# DSP.net
KiCad netlist of a schematic drawn in Altium Designer
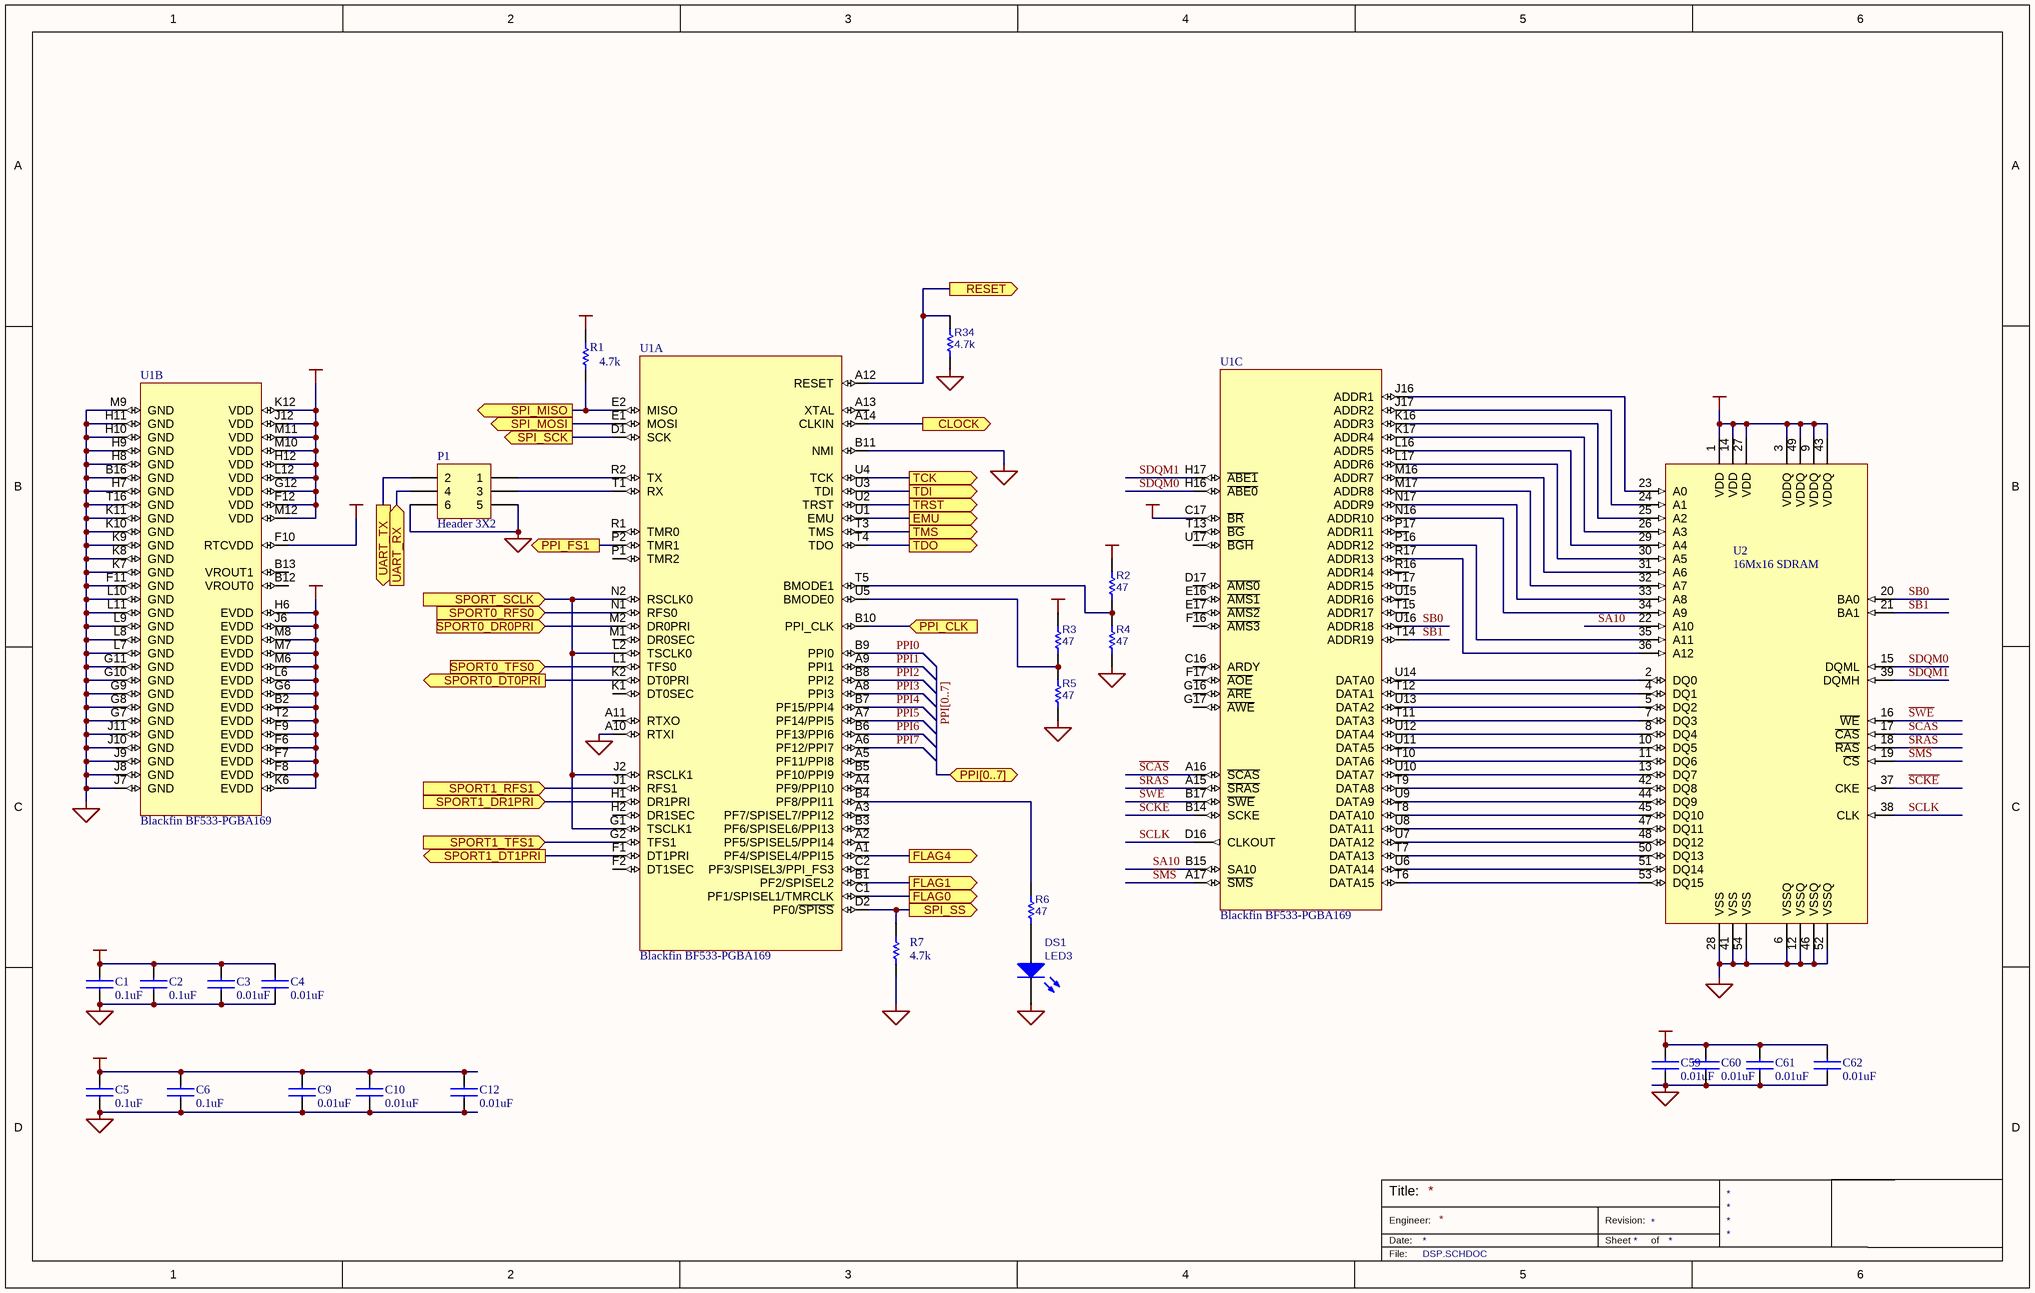
[diagram p0: DSP.SCHDOC]

(export (version "E")
  (design (tool "Eeschema 10.0.6"))
  (components
    (comp (ref "C1")
      (value "0.1uF")
      (footprint "0603")
      (description "Standard Capacitor")
      (fields (field (name "Comment") "CAPACITOR"))
      (libsource (lib "parts") (part "CAPACITOR"))
    )
    (comp (ref "C2")
      (value "0.1uF")
      (footprint "0603")
      (description "Standard Capacitor")
      (fields (field (name "Comment") "CAPACITOR"))
      (libsource (lib "parts") (part "CAPACITOR"))
    )
    (comp (ref "C3")
      (value "0.01uF")
      (footprint "0402")
      (description "Standard Capacitor")
      (fields (field (name "Comment") "CAPACITOR"))
      (libsource (lib "parts") (part "CAPACITOR"))
    )
    (comp (ref "C4")
      (value "0.01uF")
      (footprint "0402")
      (description "Standard Capacitor")
      (fields (field (name "Comment") "CAPACITOR"))
      (libsource (lib "parts") (part "CAPACITOR"))
    )
    (comp (ref "C5")
      (value "0.1uF")
      (footprint "0603")
      (description "Standard Capacitor")
      (fields (field (name "Comment") "CAPACITOR"))
      (libsource (lib "parts") (part "CAPACITOR"))
    )
    (comp (ref "C6")
      (value "0.1uF")
      (footprint "0603")
      (description "Standard Capacitor")
      (fields (field (name "Comment") "CAPACITOR"))
      (libsource (lib "parts") (part "CAPACITOR"))
    )
    (comp (ref "C9")
      (value "0.01uF")
      (footprint "0402")
      (description "Standard Capacitor")
      (fields (field (name "Comment") "CAPACITOR"))
      (libsource (lib "parts") (part "CAPACITOR"))
    )
    (comp (ref "C10")
      (value "0.01uF")
      (footprint "0402")
      (description "Standard Capacitor")
      (fields (field (name "Comment") "CAPACITOR"))
      (libsource (lib "parts") (part "CAPACITOR"))
    )
    (comp (ref "C12")
      (value "0.01uF")
      (footprint "0402")
      (description "Standard Capacitor")
      (fields (field (name "Comment") "CAPACITOR"))
      (libsource (lib "parts") (part "CAPACITOR"))
    )
    (comp (ref "C59")
      (value "0.01uF")
      (footprint "0402")
      (description "Standard Capacitor")
      (fields (field (name "Comment") "CAPACITOR"))
      (libsource (lib "parts") (part "CAPACITOR"))
    )
    (comp (ref "C60")
      (value "0.01uF")
      (footprint "0402")
      (description "Standard Capacitor")
      (fields (field (name "Comment") "CAPACITOR"))
      (libsource (lib "parts") (part "CAPACITOR"))
    )
    (comp (ref "C61")
      (value "0.01uF")
      (footprint "0402")
      (description "Standard Capacitor")
      (fields (field (name "Comment") "CAPACITOR"))
      (libsource (lib "parts") (part "CAPACITOR"))
    )
    (comp (ref "C62")
      (value "0.01uF")
      (footprint "0402")
      (description "Standard Capacitor")
      (fields (field (name "Comment") "CAPACITOR"))
      (libsource (lib "parts") (part "CAPACITOR"))
    )
    (comp (ref "DS1")
      (value "LED3")
      (footprint "LED0805")
      (description "Typical BLUE SiC LED")
      (fields (field (name "PUBLISHER") "Altium Limited"))
      (libsource (lib "Miscellaneous Devices") (part "LED3"))
    )
    (comp (ref "P1")
      (value "Header 3X2")
      (footprint "HDR2X3")
      (description "Header, 3-Pin, Dual row")
      (fields (field (name "PUBLISHER") "Altium Limited"))
      (libsource (lib "Miscellaneous Connectors") (part "Header 3X2"))
    )
    (comp (ref "R1")
      (value "4.7k")
      (footprint "0603")
      (description "Standard Passive Resistor")
      (fields (field (name "TOLERANCE") "1%") (field (name "Comment") "RESISTOR"))
      (libsource (lib "parts") (part "RESISTOR"))
    )
    (comp (ref "R2")
      (value "47")
      (footprint "0603")
      (description "Standard Passive Resistor")
      (fields (field (name "TOLERANCE") "1%") (field (name "Comment") "RESISTOR"))
      (libsource (lib "parts") (part "RESISTOR"))
    )
    (comp (ref "R3")
      (value "47")
      (footprint "0603")
      (description "Standard Passive Resistor")
      (fields (field (name "TOLERANCE") "1%") (field (name "Comment") "RESISTOR"))
      (libsource (lib "parts") (part "RESISTOR"))
    )
    (comp (ref "R4")
      (value "47")
      (footprint "0603")
      (description "Standard Passive Resistor")
      (fields (field (name "TOLERANCE") "1%") (field (name "Comment") "RESISTOR"))
      (libsource (lib "parts") (part "RESISTOR"))
    )
    (comp (ref "R5")
      (value "47")
      (footprint "0603")
      (description "Standard Passive Resistor")
      (fields (field (name "TOLERANCE") "1%") (field (name "Comment") "RESISTOR"))
      (libsource (lib "parts") (part "RESISTOR"))
    )
    (comp (ref "R6")
      (value "47")
      (footprint "0603")
      (description "Standard Passive Resistor")
      (fields (field (name "TOLERANCE") "1%") (field (name "Comment") "RESISTOR"))
      (libsource (lib "parts") (part "RESISTOR"))
    )
    (comp (ref "R7")
      (value "4.7k")
      (footprint "0603")
      (description "Standard Passive Resistor")
      (fields (field (name "TOLERANCE") "1%") (field (name "Comment") "RESISTOR"))
      (libsource (lib "parts") (part "RESISTOR"))
    )
    (comp (ref "R34")
      (value "4.7k")
      (footprint "0603")
      (description "Standard Passive Resistor")
      (fields (field (name "TOLERANCE") "1%") (field (name "Comment") "RESISTOR"))
      (libsource (lib "parts") (part "RESISTOR"))
    )
    (comp (ref "U1")
      (value "Blackfin BF533-PGBA169")
      (footprint "AD PBGA-169")
      (description "Analog Devices Blackfin")
      (libsource (lib "parts") (part "ADSP-BF53x-PBGA169"))
    )
    (comp (ref "U2")
      (value "16Mx16 SDRAM")
      (footprint "SO-G54/X.5")
      (description "Micron 16Mbitx16 SDRAM")
      (libsource (lib "parts") (part "MT48LC16M16A2TG"))
    )
  )
  (nets
    (net (code "1") (name "+1.2VCC") (class "Default")
      (node (ref "C1") (pin "2") (pintype "passive"))
      (node (ref "C2") (pin "2") (pintype "passive"))
      (node (ref "C3") (pin "2") (pintype "passive"))
      (node (ref "C4") (pin "2") (pintype "passive"))
      (node (ref "U1") (pin "F12") (pinfunction "VDD_F12") (pintype "bidirectional"))
      (node (ref "U1") (pin "G12") (pinfunction "VDD_G12") (pintype "bidirectional"))
      (node (ref "U1") (pin "H12") (pinfunction "VDD_H12") (pintype "bidirectional"))
      (node (ref "U1") (pin "J12") (pinfunction "VDD_J12") (pintype "bidirectional"))
      (node (ref "U1") (pin "K12") (pinfunction "VDD_K12") (pintype "bidirectional"))
      (node (ref "U1") (pin "L12") (pinfunction "VDD_L12") (pintype "bidirectional"))
      (node (ref "U1") (pin "M10") (pinfunction "VDD_M10") (pintype "bidirectional"))
      (node (ref "U1") (pin "M11") (pinfunction "VDD_M11") (pintype "bidirectional"))
      (node (ref "U1") (pin "M12") (pinfunction "VDD_M12") (pintype "bidirectional"))
    )
    (net (code "2") (name "/CLOCK") (class "Default")
      (node (ref "U1") (pin "A14") (pinfunction "CLKIN_A14") (pintype "bidirectional"))
    )
    (net (code "3") (name "/EMU") (class "Default")
      (node (ref "U1") (pin "U1") (pinfunction "EMU_U1") (pintype "bidirectional"))
    )
    (net (code "4") (name "/FLAG0") (class "Default")
      (node (ref "U1") (pin "C1") (pinfunction "PF1/SPISEL1/TMRCLK_C1") (pintype "bidirectional"))
    )
    (net (code "5") (name "/FLAG1") (class "Default")
      (node (ref "U1") (pin "B1") (pinfunction "PF2/SPISEL2_B1") (pintype "bidirectional"))
    )
    (net (code "6") (name "/FLAG4") (class "Default")
      (node (ref "U1") (pin "A1") (pinfunction "PF4/SPISEL4/PPI15_A1") (pintype "bidirectional"))
    )
    (net (code "7") (name "/PPI0") (class "Default")
      (node (ref "U1") (pin "B9") (pinfunction "PPI0_B9") (pintype "bidirectional"))
    )
    (net (code "8") (name "/PPI1") (class "Default")
      (node (ref "U1") (pin "A9") (pinfunction "PPI1_A9") (pintype "bidirectional"))
    )
    (net (code "9") (name "/PPI2") (class "Default")
      (node (ref "U1") (pin "B8") (pinfunction "PPI2_B8") (pintype "bidirectional"))
    )
    (net (code "10") (name "/PPI3") (class "Default")
      (node (ref "U1") (pin "A8") (pinfunction "PPI3_A8") (pintype "bidirectional"))
    )
    (net (code "11") (name "/PPI4") (class "Default")
      (node (ref "U1") (pin "B7") (pinfunction "PF15/PPI4_B7") (pintype "bidirectional"))
    )
    (net (code "12") (name "/PPI5") (class "Default")
      (node (ref "U1") (pin "A7") (pinfunction "PF14/PPI5_A7") (pintype "bidirectional"))
    )
    (net (code "13") (name "/PPI6") (class "Default")
      (node (ref "U1") (pin "B6") (pinfunction "PF13/PPI6_B6") (pintype "bidirectional"))
    )
    (net (code "14") (name "/PPI7") (class "Default")
      (node (ref "U1") (pin "A6") (pinfunction "PF12/PPI7_A6") (pintype "bidirectional"))
    )
    (net (code "16") (name "/PPI_CLK") (class "Default")
      (node (ref "U1") (pin "B10") (pinfunction "PPI_CLK_B10") (pintype "bidirectional"))
    )
    (net (code "17") (name "/PPI_FS1") (class "Default")
      (node (ref "U1") (pin "P2") (pinfunction "TMR1_P2") (pintype "bidirectional"))
    )
    (net (code "18") (name "/RESET") (class "Default")
      (node (ref "R34") (pin "1") (pintype "passive"))
      (node (ref "U1") (pin "A12") (pinfunction "RESET_A12") (pintype "bidirectional"))
    )
    (net (code "19") (name "/SA10") (class "Default")
      (node (ref "U1") (pin "B15") (pinfunction "SA10_B15") (pintype "bidirectional"))
      (node (ref "U2") (pin "22") (pinfunction "A10_22") (pintype "input"))
    )
    (net (code "20") (name "/SB0") (class "Default")
      (node (ref "U1") (pin "U16") (pinfunction "ADDR18_U16") (pintype "bidirectional"))
      (node (ref "U2") (pin "20") (pinfunction "BA0_20") (pintype "input"))
    )
    (net (code "21") (name "/SB1") (class "Default")
      (node (ref "U1") (pin "T14") (pinfunction "ADDR19_T14") (pintype "bidirectional"))
      (node (ref "U2") (pin "21") (pinfunction "BA1_21") (pintype "input"))
    )
    (net (code "22") (name "/SCLK") (class "Default")
      (node (ref "U1") (pin "D16") (pinfunction "CLKOUT_D16") (pintype "output"))
      (node (ref "U2") (pin "38") (pinfunction "CLK_38") (pintype "input"))
    )
    (net (code "23") (name "/SDQM0") (class "Default")
      (node (ref "U1") (pin "H16") (pinfunction "~{ABE0}_H16") (pintype "bidirectional"))
      (node (ref "U2") (pin "15") (pinfunction "DQML_15") (pintype "input"))
    )
    (net (code "24") (name "/SDQM1") (class "Default")
      (node (ref "U1") (pin "H17") (pinfunction "~{ABE1}_H17") (pintype "bidirectional"))
      (node (ref "U2") (pin "39") (pinfunction "DQMH_39") (pintype "input"))
    )
    (net (code "25") (name "/SPI_MISO") (class "Default")
      (node (ref "R1") (pin "1") (pintype "passive"))
      (node (ref "U1") (pin "E2") (pinfunction "MISO_E2") (pintype "bidirectional"))
    )
    (net (code "26") (name "/SPI_MOSI") (class "Default")
      (node (ref "U1") (pin "E1") (pinfunction "MOSI_E1") (pintype "bidirectional"))
    )
    (net (code "27") (name "/SPI_SCK") (class "Default")
      (node (ref "U1") (pin "D1") (pinfunction "SCK_D1") (pintype "bidirectional"))
    )
    (net (code "28") (name "/SPI_SS") (class "Default")
      (node (ref "R7") (pin "2") (pintype "passive"))
      (node (ref "U1") (pin "D2") (pinfunction "PF0/~{SPISS}_D2") (pintype "bidirectional"))
    )
    (net (code "29") (name "/SPORT0_DR0PRI") (class "Default")
      (node (ref "U1") (pin "M2") (pinfunction "DR0PRI_M2") (pintype "bidirectional"))
    )
    (net (code "30") (name "/SPORT0_DT0PRI") (class "Default")
      (node (ref "U1") (pin "K2") (pinfunction "DT0PRI_K2") (pintype "bidirectional"))
    )
    (net (code "31") (name "/SPORT0_RFS0") (class "Default")
      (node (ref "U1") (pin "N1") (pinfunction "RFS0_N1") (pintype "bidirectional"))
    )
    (net (code "32") (name "/SPORT0_TFS0") (class "Default")
      (node (ref "U1") (pin "L1") (pinfunction "TFS0_L1") (pintype "bidirectional"))
    )
    (net (code "33") (name "/SPORT1_DR1PRI") (class "Default")
      (node (ref "U1") (pin "H1") (pinfunction "DR1PRI_H1") (pintype "bidirectional"))
    )
    (net (code "34") (name "/SPORT1_DT1PRI") (class "Default")
      (node (ref "U1") (pin "F1") (pinfunction "DT1PRI_F1") (pintype "bidirectional"))
    )
    (net (code "35") (name "/SPORT1_RFS1") (class "Default")
      (node (ref "U1") (pin "J1") (pinfunction "RFS1_J1") (pintype "bidirectional"))
    )
    (net (code "36") (name "/SPORT1_TFS1") (class "Default")
      (node (ref "U1") (pin "G2") (pinfunction "TFS1_G2") (pintype "bidirectional"))
    )
    (net (code "37") (name "/SPORT_SCLK") (class "Default")
      (node (ref "U1") (pin "G1") (pinfunction "TSCLK1_G1") (pintype "bidirectional"))
      (node (ref "U1") (pin "J2") (pinfunction "RSCLK1_J2") (pintype "bidirectional"))
      (node (ref "U1") (pin "L2") (pinfunction "TSCLK0_L2") (pintype "bidirectional"))
      (node (ref "U1") (pin "N2") (pinfunction "RSCLK0_N2") (pintype "bidirectional"))
    )
    (net (code "38") (name "/TCK") (class "Default")
      (node (ref "U1") (pin "U4") (pinfunction "TCK_U4") (pintype "bidirectional"))
    )
    (net (code "39") (name "/TDI") (class "Default")
      (node (ref "U1") (pin "U3") (pinfunction "TDI_U3") (pintype "bidirectional"))
    )
    (net (code "40") (name "/TDO") (class "Default")
      (node (ref "U1") (pin "T4") (pinfunction "TDO_T4") (pintype "bidirectional"))
    )
    (net (code "41") (name "/TMS") (class "Default")
      (node (ref "U1") (pin "T3") (pinfunction "TMS_T3") (pintype "bidirectional"))
    )
    (net (code "42") (name "/TRST") (class "Default")
      (node (ref "U1") (pin "U2") (pinfunction "TRST_U2") (pintype "bidirectional"))
    )
    (net (code "43") (name "/UART_RX") (class "Default")
      (node (ref "P1") (pin "4") (pinfunction "4_4") (pintype "passive"))
    )
    (net (code "44") (name "/UART_TX") (class "Default")
      (node (ref "P1") (pin "2") (pinfunction "2_2") (pintype "passive"))
    )
    (net (code "45") (name "/~{SCAS}") (class "Default")
      (node (ref "U1") (pin "A16") (pinfunction "~{SCAS}_A16") (pintype "bidirectional"))
      (node (ref "U2") (pin "17") (pinfunction "~{CAS}_17") (pintype "input"))
    )
    (net (code "46") (name "/~{SCKE}") (class "Default")
      (node (ref "U1") (pin "B14") (pinfunction "SCKE_B14") (pintype "bidirectional"))
      (node (ref "U2") (pin "37") (pinfunction "CKE_37") (pintype "input"))
    )
    (net (code "47") (name "/~{SMS}") (class "Default")
      (node (ref "U1") (pin "A17") (pinfunction "~{SMS}_A17") (pintype "bidirectional"))
      (node (ref "U2") (pin "19") (pinfunction "~{CS}_19") (pintype "input"))
    )
    (net (code "48") (name "/~{SRAS}") (class "Default")
      (node (ref "U1") (pin "A15") (pinfunction "~{SRAS}_A15") (pintype "bidirectional"))
      (node (ref "U2") (pin "18") (pinfunction "~{RAS}_18") (pintype "input"))
    )
    (net (code "49") (name "/~{SWE}") (class "Default")
      (node (ref "U1") (pin "B17") (pinfunction "~{SWE}_B17") (pintype "bidirectional"))
      (node (ref "U2") (pin "16") (pinfunction "~{WE}_16") (pintype "input"))
    )
    (net (code "50") (name "GND") (class "Default")
      (node (ref "C1") (pin "1") (pintype "passive"))
      (node (ref "C10") (pin "1") (pintype "passive"))
      (node (ref "C12") (pin "1") (pintype "passive"))
      (node (ref "C2") (pin "1") (pintype "passive"))
      (node (ref "C3") (pin "1") (pintype "passive"))
      (node (ref "C4") (pin "1") (pintype "passive"))
      (node (ref "C5") (pin "1") (pintype "passive"))
      (node (ref "C59") (pin "1") (pintype "passive"))
      (node (ref "C6") (pin "1") (pintype "passive"))
      (node (ref "C60") (pin "1") (pintype "passive"))
      (node (ref "C61") (pin "1") (pintype "passive"))
      (node (ref "C62") (pin "1") (pintype "passive"))
      (node (ref "C9") (pin "1") (pintype "passive"))
      (node (ref "DS1") (pin "2") (pinfunction "K_2") (pintype "passive"))
      (node (ref "P1") (pin "5") (pinfunction "5_5") (pintype "passive"))
      (node (ref "P1") (pin "6") (pinfunction "6_6") (pintype "passive"))
      (node (ref "R34") (pin "2") (pintype "passive"))
      (node (ref "R4") (pin "2") (pintype "passive"))
      (node (ref "R5") (pin "2") (pintype "passive"))
      (node (ref "R7") (pin "1") (pintype "passive"))
      (node (ref "U1") (pin "A10") (pinfunction "RTXI_A10") (pintype "bidirectional"))
      (node (ref "U1") (pin "B11") (pinfunction "NMI_B11") (pintype "bidirectional"))
      (node (ref "U1") (pin "B16") (pinfunction "GND_B16") (pintype "bidirectional"))
      (node (ref "U1") (pin "F11") (pinfunction "GND_F11") (pintype "bidirectional"))
      (node (ref "U1") (pin "G10") (pinfunction "GND_G10") (pintype "bidirectional"))
      (node (ref "U1") (pin "G11") (pinfunction "GND_G11") (pintype "bidirectional"))
      (node (ref "U1") (pin "G7") (pinfunction "GND_G7") (pintype "bidirectional"))
      (node (ref "U1") (pin "G8") (pinfunction "GND_G8") (pintype "bidirectional"))
      (node (ref "U1") (pin "G9") (pinfunction "GND_G9") (pintype "bidirectional"))
      (node (ref "U1") (pin "H10") (pinfunction "GND_H10") (pintype "bidirectional"))
      (node (ref "U1") (pin "H11") (pinfunction "GND_H11") (pintype "bidirectional"))
      (node (ref "U1") (pin "H7") (pinfunction "GND_H7") (pintype "bidirectional"))
      (node (ref "U1") (pin "H8") (pinfunction "GND_H8") (pintype "bidirectional"))
      (node (ref "U1") (pin "H9") (pinfunction "GND_H9") (pintype "bidirectional"))
      (node (ref "U1") (pin "J10") (pinfunction "GND_J10") (pintype "bidirectional"))
      (node (ref "U1") (pin "J11") (pinfunction "GND_J11") (pintype "bidirectional"))
      (node (ref "U1") (pin "J7") (pinfunction "GND_J7") (pintype "bidirectional"))
      (node (ref "U1") (pin "J8") (pinfunction "GND_J8") (pintype "bidirectional"))
      (node (ref "U1") (pin "J9") (pinfunction "GND_J9") (pintype "bidirectional"))
      (node (ref "U1") (pin "K10") (pinfunction "GND_K10") (pintype "bidirectional"))
      (node (ref "U1") (pin "K11") (pinfunction "GND_K11") (pintype "bidirectional"))
      (node (ref "U1") (pin "K7") (pinfunction "GND_K7") (pintype "bidirectional"))
      (node (ref "U1") (pin "K8") (pinfunction "GND_K8") (pintype "bidirectional"))
      (node (ref "U1") (pin "K9") (pinfunction "GND_K9") (pintype "bidirectional"))
      (node (ref "U1") (pin "L10") (pinfunction "GND_L10") (pintype "bidirectional"))
      (node (ref "U1") (pin "L11") (pinfunction "GND_L11") (pintype "bidirectional"))
      (node (ref "U1") (pin "L7") (pinfunction "GND_L7") (pintype "bidirectional"))
      (node (ref "U1") (pin "L8") (pinfunction "GND_L8") (pintype "bidirectional"))
      (node (ref "U1") (pin "L9") (pinfunction "GND_L9") (pintype "bidirectional"))
      (node (ref "U1") (pin "M9") (pinfunction "GND_M9") (pintype "bidirectional"))
      (node (ref "U1") (pin "T16") (pinfunction "GND_T16") (pintype "bidirectional"))
      (node (ref "U2") (pin "12") (pinfunction "VSSQ_12") (pintype "power_in"))
      (node (ref "U2") (pin "28") (pinfunction "VSS_28") (pintype "power_in"))
      (node (ref "U2") (pin "41") (pinfunction "VSS_41") (pintype "power_in"))
      (node (ref "U2") (pin "46") (pinfunction "VSSQ_46") (pintype "power_in"))
      (node (ref "U2") (pin "52") (pinfunction "VSSQ_52") (pintype "power_in"))
      (node (ref "U2") (pin "54") (pinfunction "VSS_54") (pintype "power_in"))
      (node (ref "U2") (pin "6") (pinfunction "VSSQ_6") (pintype "power_in"))
    )
    (net (code "51") (name "Net-(DS1-A)") (class "Default")
      (node (ref "DS1") (pin "1") (pinfunction "A_1") (pintype "passive"))
      (node (ref "R6") (pin "2") (pintype "passive"))
    )
    (net (code "52") (name "Net-(U1A-BMODE0)") (class "Default")
      (node (ref "R3") (pin "2") (pintype "passive"))
      (node (ref "R5") (pin "1") (pintype "passive"))
      (node (ref "U1") (pin "U5") (pinfunction "BMODE0_U5") (pintype "bidirectional"))
    )
    (net (code "53") (name "Net-(U1A-BMODE1)") (class "Default")
      (node (ref "R2") (pin "2") (pintype "passive"))
      (node (ref "R4") (pin "1") (pintype "passive"))
      (node (ref "U1") (pin "T5") (pinfunction "BMODE1_T5") (pintype "bidirectional"))
    )
    (net (code "54") (name "Net-(U1A-PF8{slash}PPI11)") (class "Default")
      (node (ref "R6") (pin "1") (pintype "passive"))
      (node (ref "U1") (pin "B4") (pinfunction "PF8/PPI11_B4") (pintype "bidirectional"))
    )
    (net (code "55") (name "Net-(U1A-RX)") (class "Default")
      (node (ref "P1") (pin "3") (pinfunction "3_3") (pintype "passive"))
      (node (ref "U1") (pin "T1") (pinfunction "RX_T1") (pintype "bidirectional"))
    )
    (net (code "56") (name "Net-(U1A-TX)") (class "Default")
      (node (ref "P1") (pin "1") (pinfunction "1_1") (pintype "passive"))
      (node (ref "U1") (pin "R2") (pinfunction "TX_R2") (pintype "bidirectional"))
    )
    (net (code "57") (name "Net-(U1C-ADDR1)") (class "Default")
      (node (ref "U1") (pin "J16") (pinfunction "ADDR1_J16") (pintype "bidirectional"))
      (node (ref "U2") (pin "23") (pinfunction "A0_23") (pintype "input"))
    )
    (net (code "58") (name "Net-(U1C-ADDR2)") (class "Default")
      (node (ref "U1") (pin "J17") (pinfunction "ADDR2_J17") (pintype "bidirectional"))
      (node (ref "U2") (pin "24") (pinfunction "A1_24") (pintype "input"))
    )
    (net (code "59") (name "Net-(U1C-ADDR3)") (class "Default")
      (node (ref "U1") (pin "K16") (pinfunction "ADDR3_K16") (pintype "bidirectional"))
      (node (ref "U2") (pin "25") (pinfunction "A2_25") (pintype "input"))
    )
    (net (code "60") (name "Net-(U1C-ADDR4)") (class "Default")
      (node (ref "U1") (pin "K17") (pinfunction "ADDR4_K17") (pintype "bidirectional"))
      (node (ref "U2") (pin "26") (pinfunction "A3_26") (pintype "input"))
    )
    (net (code "61") (name "Net-(U1C-ADDR5)") (class "Default")
      (node (ref "U1") (pin "L16") (pinfunction "ADDR5_L16") (pintype "bidirectional"))
      (node (ref "U2") (pin "29") (pinfunction "A4_29") (pintype "input"))
    )
    (net (code "62") (name "Net-(U1C-ADDR6)") (class "Default")
      (node (ref "U1") (pin "L17") (pinfunction "ADDR6_L17") (pintype "bidirectional"))
      (node (ref "U2") (pin "30") (pinfunction "A5_30") (pintype "input"))
    )
    (net (code "63") (name "Net-(U1C-ADDR7)") (class "Default")
      (node (ref "U1") (pin "M16") (pinfunction "ADDR7_M16") (pintype "bidirectional"))
      (node (ref "U2") (pin "31") (pinfunction "A6_31") (pintype "input"))
    )
    (net (code "64") (name "Net-(U1C-ADDR8)") (class "Default")
      (node (ref "U1") (pin "M17") (pinfunction "ADDR8_M17") (pintype "bidirectional"))
      (node (ref "U2") (pin "32") (pinfunction "A7_32") (pintype "input"))
    )
    (net (code "65") (name "Net-(U1C-ADDR9)") (class "Default")
      (node (ref "U1") (pin "N17") (pinfunction "ADDR9_N17") (pintype "bidirectional"))
      (node (ref "U2") (pin "33") (pinfunction "A8_33") (pintype "input"))
    )
    (net (code "66") (name "Net-(U1C-ADDR10)") (class "Default")
      (node (ref "U1") (pin "N16") (pinfunction "ADDR10_N16") (pintype "bidirectional"))
      (node (ref "U2") (pin "34") (pinfunction "A9_34") (pintype "input"))
    )
    (net (code "67") (name "Net-(U1C-ADDR12)") (class "Default")
      (node (ref "U1") (pin "P16") (pinfunction "ADDR12_P16") (pintype "bidirectional"))
      (node (ref "U2") (pin "35") (pinfunction "A11_35") (pintype "input"))
    )
    (net (code "68") (name "Net-(U1C-ADDR13)") (class "Default")
      (node (ref "U1") (pin "R17") (pinfunction "ADDR13_R17") (pintype "bidirectional"))
      (node (ref "U2") (pin "36") (pinfunction "A12_36") (pintype "input"))
    )
    (net (code "69") (name "Net-(U1C-DATA0)") (class "Default")
      (node (ref "U1") (pin "U14") (pinfunction "DATA0_U14") (pintype "bidirectional"))
      (node (ref "U2") (pin "2") (pinfunction "DQ0_2") (pintype "bidirectional"))
    )
    (net (code "70") (name "Net-(U1C-DATA1)") (class "Default")
      (node (ref "U1") (pin "T12") (pinfunction "DATA1_T12") (pintype "bidirectional"))
      (node (ref "U2") (pin "4") (pinfunction "DQ1_4") (pintype "bidirectional"))
    )
    (net (code "71") (name "Net-(U1C-DATA2)") (class "Default")
      (node (ref "U1") (pin "U13") (pinfunction "DATA2_U13") (pintype "bidirectional"))
      (node (ref "U2") (pin "5") (pinfunction "DQ2_5") (pintype "bidirectional"))
    )
    (net (code "72") (name "Net-(U1C-DATA3)") (class "Default")
      (node (ref "U1") (pin "T11") (pinfunction "DATA3_T11") (pintype "bidirectional"))
      (node (ref "U2") (pin "7") (pinfunction "DQ3_7") (pintype "bidirectional"))
    )
    (net (code "73") (name "Net-(U1C-DATA4)") (class "Default")
      (node (ref "U1") (pin "U12") (pinfunction "DATA4_U12") (pintype "bidirectional"))
      (node (ref "U2") (pin "8") (pinfunction "DQ4_8") (pintype "bidirectional"))
    )
    (net (code "74") (name "Net-(U1C-DATA5)") (class "Default")
      (node (ref "U1") (pin "U11") (pinfunction "DATA5_U11") (pintype "bidirectional"))
      (node (ref "U2") (pin "10") (pinfunction "DQ5_10") (pintype "bidirectional"))
    )
    (net (code "75") (name "Net-(U1C-DATA6)") (class "Default")
      (node (ref "U1") (pin "T10") (pinfunction "DATA6_T10") (pintype "bidirectional"))
      (node (ref "U2") (pin "11") (pinfunction "DQ6_11") (pintype "bidirectional"))
    )
    (net (code "76") (name "Net-(U1C-DATA7)") (class "Default")
      (node (ref "U1") (pin "U10") (pinfunction "DATA7_U10") (pintype "bidirectional"))
      (node (ref "U2") (pin "13") (pinfunction "DQ7_13") (pintype "bidirectional"))
    )
    (net (code "77") (name "Net-(U1C-DATA8)") (class "Default")
      (node (ref "U1") (pin "T9") (pinfunction "DATA8_T9") (pintype "bidirectional"))
      (node (ref "U2") (pin "42") (pinfunction "DQ8_42") (pintype "bidirectional"))
    )
    (net (code "78") (name "Net-(U1C-DATA9)") (class "Default")
      (node (ref "U1") (pin "U9") (pinfunction "DATA9_U9") (pintype "bidirectional"))
      (node (ref "U2") (pin "44") (pinfunction "DQ9_44") (pintype "bidirectional"))
    )
    (net (code "79") (name "Net-(U1C-DATA10)") (class "Default")
      (node (ref "U1") (pin "T8") (pinfunction "DATA10_T8") (pintype "bidirectional"))
      (node (ref "U2") (pin "45") (pinfunction "DQ10_45") (pintype "bidirectional"))
    )
    (net (code "80") (name "Net-(U1C-DATA11)") (class "Default")
      (node (ref "U1") (pin "U8") (pinfunction "DATA11_U8") (pintype "bidirectional"))
      (node (ref "U2") (pin "47") (pinfunction "DQ11_47") (pintype "bidirectional"))
    )
    (net (code "81") (name "Net-(U1C-DATA12)") (class "Default")
      (node (ref "U1") (pin "U7") (pinfunction "DATA12_U7") (pintype "bidirectional"))
      (node (ref "U2") (pin "48") (pinfunction "DQ12_48") (pintype "bidirectional"))
    )
    (net (code "82") (name "Net-(U1C-DATA13)") (class "Default")
      (node (ref "U1") (pin "T7") (pinfunction "DATA13_T7") (pintype "bidirectional"))
      (node (ref "U2") (pin "50") (pinfunction "DQ13_50") (pintype "bidirectional"))
    )
    (net (code "83") (name "Net-(U1C-DATA14)") (class "Default")
      (node (ref "U1") (pin "U6") (pinfunction "DATA14_U6") (pintype "bidirectional"))
      (node (ref "U2") (pin "51") (pinfunction "DQ14_51") (pintype "bidirectional"))
    )
    (net (code "84") (name "Net-(U1C-DATA15)") (class "Default")
      (node (ref "U1") (pin "T6") (pinfunction "DATA15_T6") (pintype "bidirectional"))
      (node (ref "U2") (pin "53") (pinfunction "DQ15_53") (pintype "bidirectional"))
    )
    (net (code "85") (name "VCC") (class "Default")
      (node (ref "C10") (pin "2") (pintype "passive"))
      (node (ref "C12") (pin "2") (pintype "passive"))
      (node (ref "C5") (pin "2") (pintype "passive"))
      (node (ref "C59") (pin "2") (pintype "passive"))
      (node (ref "C6") (pin "2") (pintype "passive"))
      (node (ref "C60") (pin "2") (pintype "passive"))
      (node (ref "C61") (pin "2") (pintype "passive"))
      (node (ref "C62") (pin "2") (pintype "passive"))
      (node (ref "C9") (pin "2") (pintype "passive"))
      (node (ref "R1") (pin "2") (pintype "passive"))
      (node (ref "R2") (pin "1") (pintype "passive"))
      (node (ref "R3") (pin "1") (pintype "passive"))
      (node (ref "U1") (pin "B2") (pinfunction "EVDD_B2") (pintype "bidirectional"))
      (node (ref "U1") (pin "C17") (pinfunction "~{BR}_C17") (pintype "bidirectional"))
      (node (ref "U1") (pin "F10") (pinfunction "RTCVDD_F10") (pintype "bidirectional"))
      (node (ref "U1") (pin "F6") (pinfunction "EVDD_F6") (pintype "bidirectional"))
      (node (ref "U1") (pin "F7") (pinfunction "EVDD_F7") (pintype "bidirectional"))
      (node (ref "U1") (pin "F8") (pinfunction "EVDD_F8") (pintype "bidirectional"))
      (node (ref "U1") (pin "F9") (pinfunction "EVDD_F9") (pintype "bidirectional"))
      (node (ref "U1") (pin "G6") (pinfunction "EVDD_G6") (pintype "bidirectional"))
      (node (ref "U1") (pin "H6") (pinfunction "EVDD_H6") (pintype "bidirectional"))
      (node (ref "U1") (pin "J6") (pinfunction "EVDD_J6") (pintype "bidirectional"))
      (node (ref "U1") (pin "K6") (pinfunction "EVDD_K6") (pintype "bidirectional"))
      (node (ref "U1") (pin "L6") (pinfunction "EVDD_L6") (pintype "bidirectional"))
      (node (ref "U1") (pin "M6") (pinfunction "EVDD_M6") (pintype "bidirectional"))
      (node (ref "U1") (pin "M7") (pinfunction "EVDD_M7") (pintype "bidirectional"))
      (node (ref "U1") (pin "M8") (pinfunction "EVDD_M8") (pintype "bidirectional"))
      (node (ref "U1") (pin "T2") (pinfunction "EVDD_T2") (pintype "bidirectional"))
      (node (ref "U2") (pin "1") (pinfunction "VDD_1") (pintype "power_in"))
      (node (ref "U2") (pin "14") (pinfunction "VDD_14") (pintype "power_in"))
      (node (ref "U2") (pin "27") (pinfunction "VDD_27") (pintype "power_in"))
      (node (ref "U2") (pin "3") (pinfunction "VDDQ_3") (pintype "power_in"))
      (node (ref "U2") (pin "43") (pinfunction "VDDQ_43") (pintype "power_in"))
      (node (ref "U2") (pin "49") (pinfunction "VDDQ_49") (pintype "power_in"))
      (node (ref "U2") (pin "9") (pinfunction "VDDQ_9") (pintype "power_in"))
    )
    (net (code "86") (name "unconnected-(U1A-DR0SEC-PadM1)") (class "Default")
      (node (ref "U1") (pin "M1") (pinfunction "DR0SEC_M1") (pintype "bidirectional"))
    )
    (net (code "87") (name "unconnected-(U1A-DR1SEC-PadH2)") (class "Default")
      (node (ref "U1") (pin "H2") (pinfunction "DR1SEC_H2") (pintype "bidirectional"))
    )
    (net (code "88") (name "unconnected-(U1A-DT0SEC-PadK1)") (class "Default")
      (node (ref "U1") (pin "K1") (pinfunction "DT0SEC_K1") (pintype "bidirectional"))
    )
    (net (code "89") (name "unconnected-(U1A-DT1SEC-PadF2)") (class "Default")
      (node (ref "U1") (pin "F2") (pinfunction "DT1SEC_F2") (pintype "bidirectional"))
    )
    (net (code "90") (name "unconnected-(U1A-PF3{slash}SPISEL3{slash}PPI_FS3-PadC2)") (class "Default")
      (node (ref "U1") (pin "C2") (pinfunction "PF3/SPISEL3/PPI_FS3_C2") (pintype "bidirectional"))
    )
    (net (code "91") (name "unconnected-(U1A-PF5{slash}SPISEL5{slash}PPI14-PadA2)") (class "Default")
      (node (ref "U1") (pin "A2") (pinfunction "PF5/SPISEL5/PPI14_A2") (pintype "bidirectional"))
    )
    (net (code "92") (name "unconnected-(U1A-PF6{slash}SPISEL6{slash}PPI13-PadB3)") (class "Default")
      (node (ref "U1") (pin "B3") (pinfunction "PF6/SPISEL6/PPI13_B3") (pintype "bidirectional"))
    )
    (net (code "93") (name "unconnected-(U1A-PF7{slash}SPISEL7{slash}PPI12-PadA3)") (class "Default")
      (node (ref "U1") (pin "A3") (pinfunction "PF7/SPISEL7/PPI12_A3") (pintype "bidirectional"))
    )
    (net (code "94") (name "unconnected-(U1A-PF9{slash}PPI10-PadA4)") (class "Default")
      (node (ref "U1") (pin "A4") (pinfunction "PF9/PPI10_A4") (pintype "bidirectional"))
    )
    (net (code "95") (name "unconnected-(U1A-PF10{slash}PPI9-PadB5)") (class "Default")
      (node (ref "U1") (pin "B5") (pinfunction "PF10/PPI9_B5") (pintype "bidirectional"))
    )
    (net (code "96") (name "unconnected-(U1A-PF11{slash}PPI8-PadA5)") (class "Default")
      (node (ref "U1") (pin "A5") (pinfunction "PF11/PPI8_A5") (pintype "bidirectional"))
    )
    (net (code "97") (name "unconnected-(U1A-RTXO-PadA11)") (class "Default")
      (node (ref "U1") (pin "A11") (pinfunction "RTXO_A11") (pintype "bidirectional"))
    )
    (net (code "98") (name "unconnected-(U1A-TMR0-PadR1)") (class "Default")
      (node (ref "U1") (pin "R1") (pinfunction "TMR0_R1") (pintype "bidirectional"))
    )
    (net (code "99") (name "unconnected-(U1A-TMR2-PadP1)") (class "Default")
      (node (ref "U1") (pin "P1") (pinfunction "TMR2_P1") (pintype "bidirectional"))
    )
    (net (code "100") (name "unconnected-(U1A-XTAL-PadA13)") (class "Default")
      (node (ref "U1") (pin "A13") (pinfunction "XTAL_A13") (pintype "bidirectional"))
    )
    (net (code "101") (name "unconnected-(U1B-VROUT0-PadB12)") (class "Default")
      (node (ref "U1") (pin "B12") (pinfunction "VROUT0_B12") (pintype "bidirectional"))
    )
    (net (code "102") (name "unconnected-(U1B-VROUT1-PadB13)") (class "Default")
      (node (ref "U1") (pin "B13") (pinfunction "VROUT1_B13") (pintype "bidirectional"))
    )
    (net (code "103") (name "unconnected-(U1C-ADDR11-PadP17)") (class "Default")
      (node (ref "U1") (pin "P17") (pinfunction "ADDR11_P17") (pintype "bidirectional"))
    )
    (net (code "104") (name "unconnected-(U1C-ADDR14-PadR16)") (class "Default")
      (node (ref "U1") (pin "R16") (pinfunction "ADDR14_R16") (pintype "bidirectional"))
    )
    (net (code "105") (name "unconnected-(U1C-ADDR15-PadT17)") (class "Default")
      (node (ref "U1") (pin "T17") (pinfunction "ADDR15_T17") (pintype "bidirectional"))
    )
    (net (code "106") (name "unconnected-(U1C-ADDR16-PadU15)") (class "Default")
      (node (ref "U1") (pin "U15") (pinfunction "ADDR16_U15") (pintype "bidirectional"))
    )
    (net (code "107") (name "unconnected-(U1C-ADDR17-PadT15)") (class "Default")
      (node (ref "U1") (pin "T15") (pinfunction "ADDR17_T15") (pintype "bidirectional"))
    )
    (net (code "108") (name "unconnected-(U1C-ARDY-PadC16)") (class "Default")
      (node (ref "U1") (pin "C16") (pinfunction "ARDY_C16") (pintype "bidirectional"))
    )
    (net (code "109") (name "unconnected-(U1C-~{AMS0}-PadD17)") (class "Default")
      (node (ref "U1") (pin "D17") (pinfunction "~{AMS0}_D17") (pintype "bidirectional"))
    )
    (net (code "110") (name "unconnected-(U1C-~{AMS1}-PadE16)") (class "Default")
      (node (ref "U1") (pin "E16") (pinfunction "~{AMS1}_E16") (pintype "bidirectional"))
    )
    (net (code "111") (name "unconnected-(U1C-~{AMS2}-PadE17)") (class "Default")
      (node (ref "U1") (pin "E17") (pinfunction "~{AMS2}_E17") (pintype "bidirectional"))
    )
    (net (code "112") (name "unconnected-(U1C-~{AMS3}-PadF16)") (class "Default")
      (node (ref "U1") (pin "F16") (pinfunction "~{AMS3}_F16") (pintype "bidirectional"))
    )
    (net (code "113") (name "unconnected-(U1C-~{AOE}-PadF17)") (class "Default")
      (node (ref "U1") (pin "F17") (pinfunction "~{AOE}_F17") (pintype "bidirectional"))
    )
    (net (code "114") (name "unconnected-(U1C-~{ARE}-PadG16)") (class "Default")
      (node (ref "U1") (pin "G16") (pinfunction "~{ARE}_G16") (pintype "bidirectional"))
    )
    (net (code "115") (name "unconnected-(U1C-~{AWE}-PadG17)") (class "Default")
      (node (ref "U1") (pin "G17") (pinfunction "~{AWE}_G17") (pintype "bidirectional"))
    )
    (net (code "116") (name "unconnected-(U1C-~{BGH}-PadU17)") (class "Default")
      (node (ref "U1") (pin "U17") (pinfunction "~{BGH}_U17") (pintype "bidirectional"))
    )
    (net (code "117") (name "unconnected-(U1C-~{BG}-PadT13)") (class "Default")
      (node (ref "U1") (pin "T13") (pinfunction "~{BG}_T13") (pintype "bidirectional"))
    )
  )
)
